# pCog102_Wifi_PSPJoy_BLED_TFT.net
KiCad netlist of a schematic drawn in EAGLE
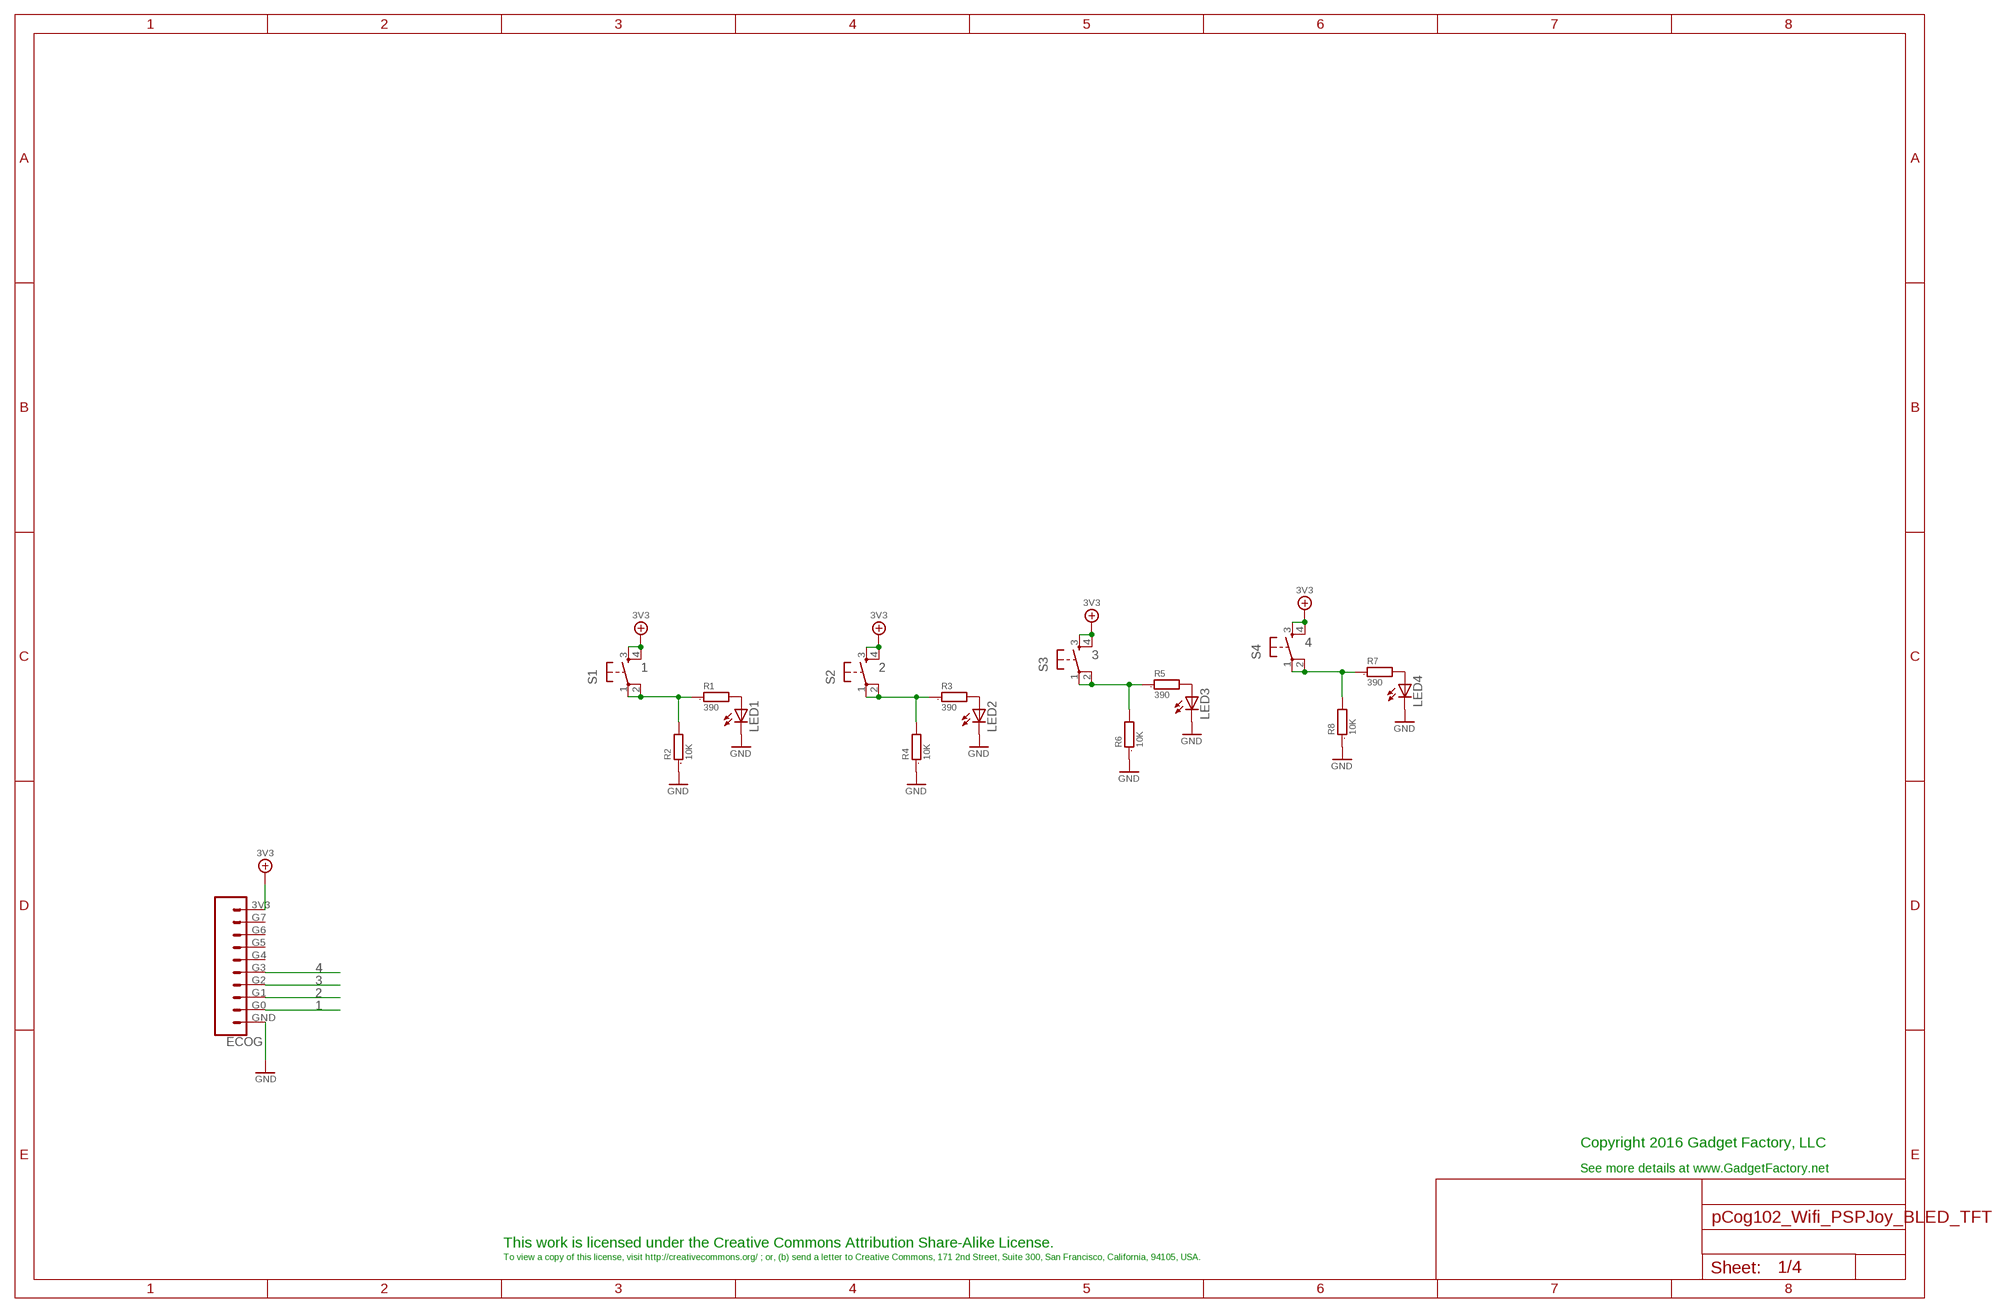
[diagram p0: schematic, sheet 1]
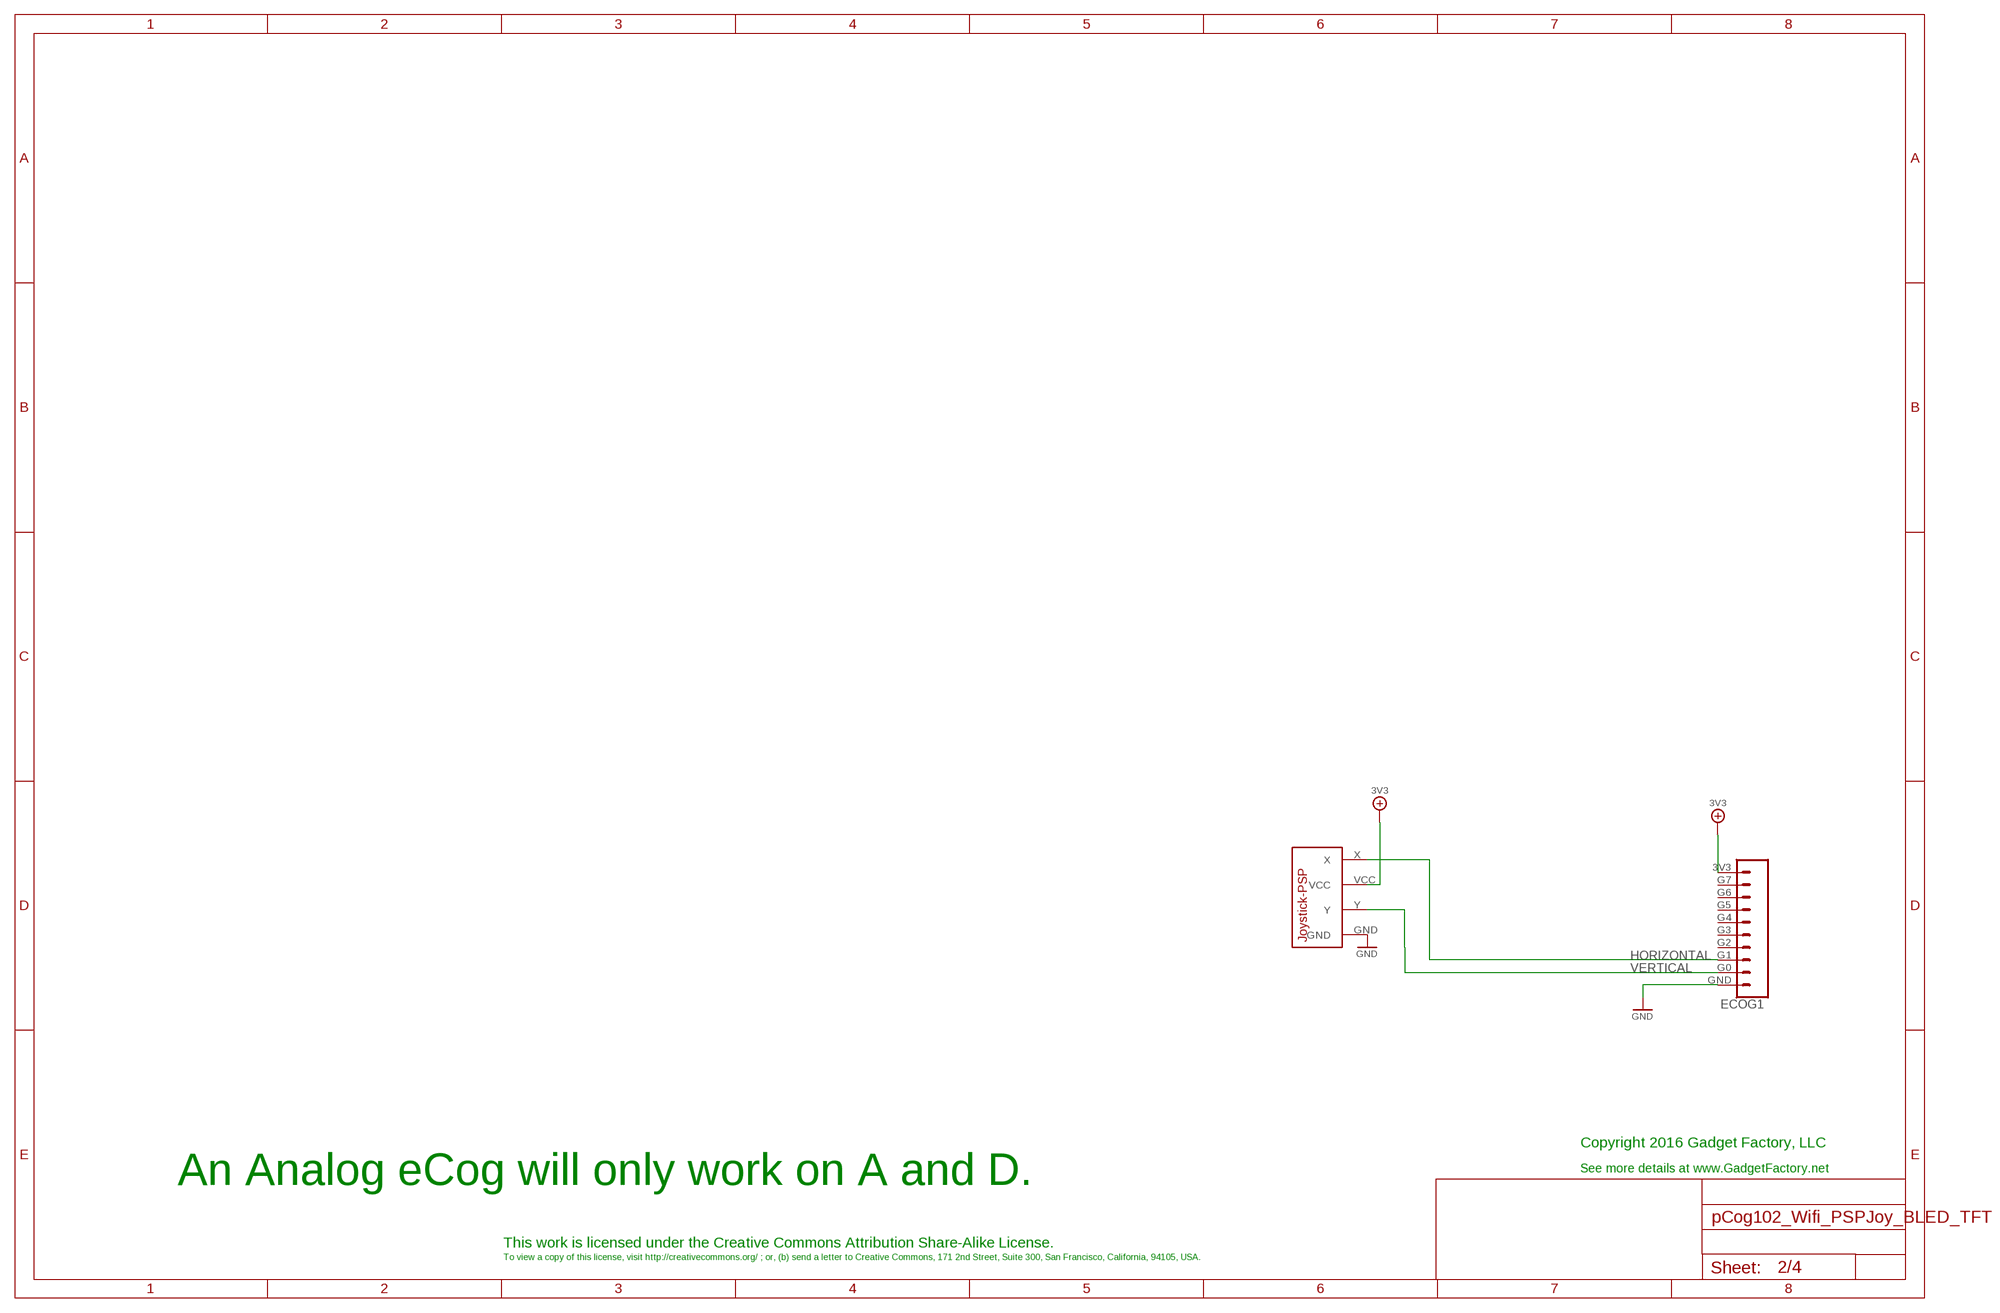
[diagram p1: schematic, sheet 2]
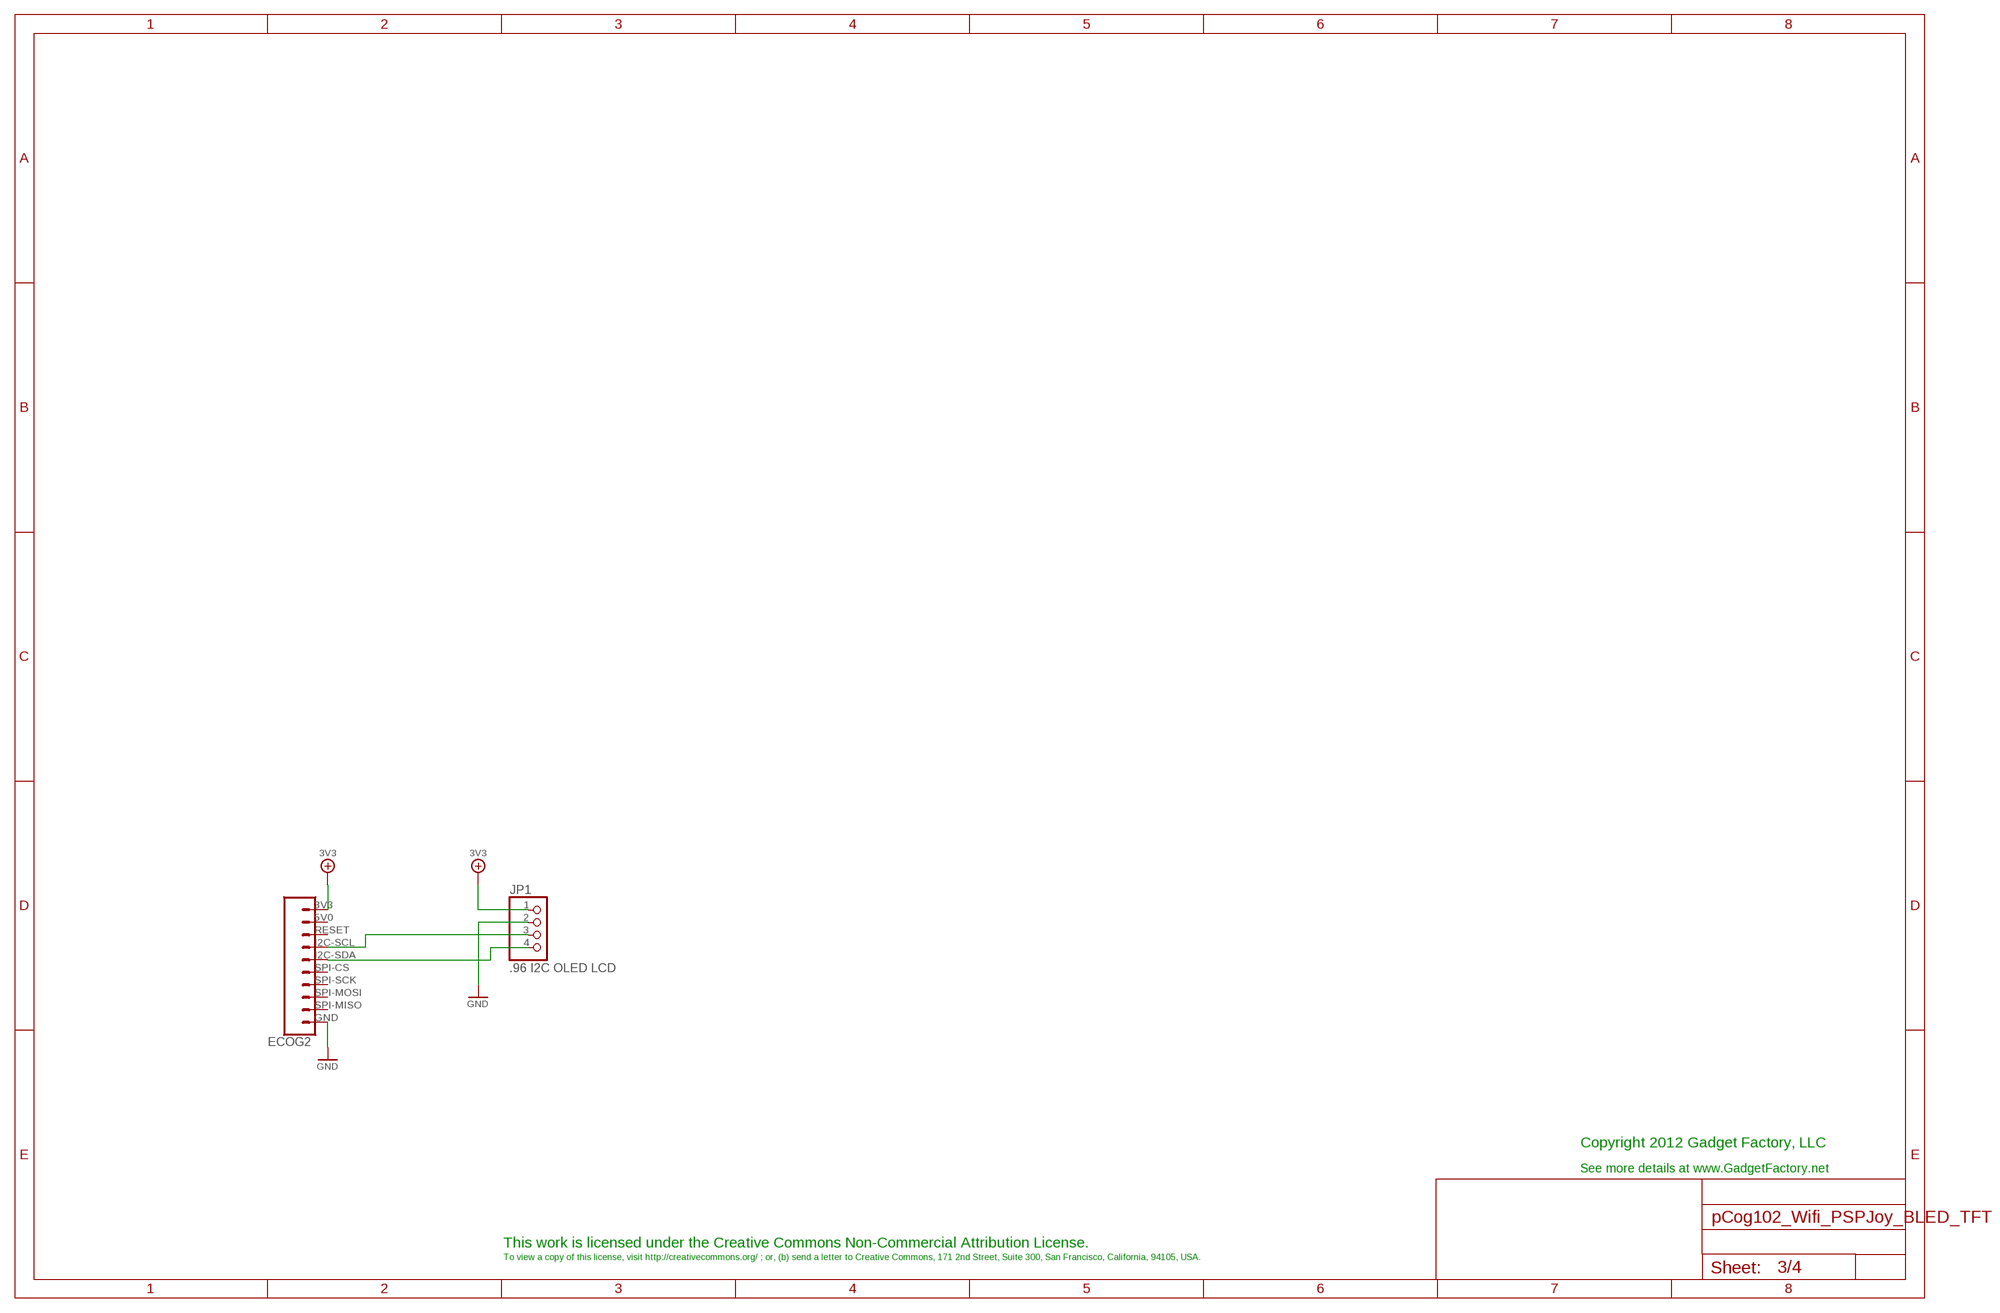
[diagram p2: schematic, sheet 3]
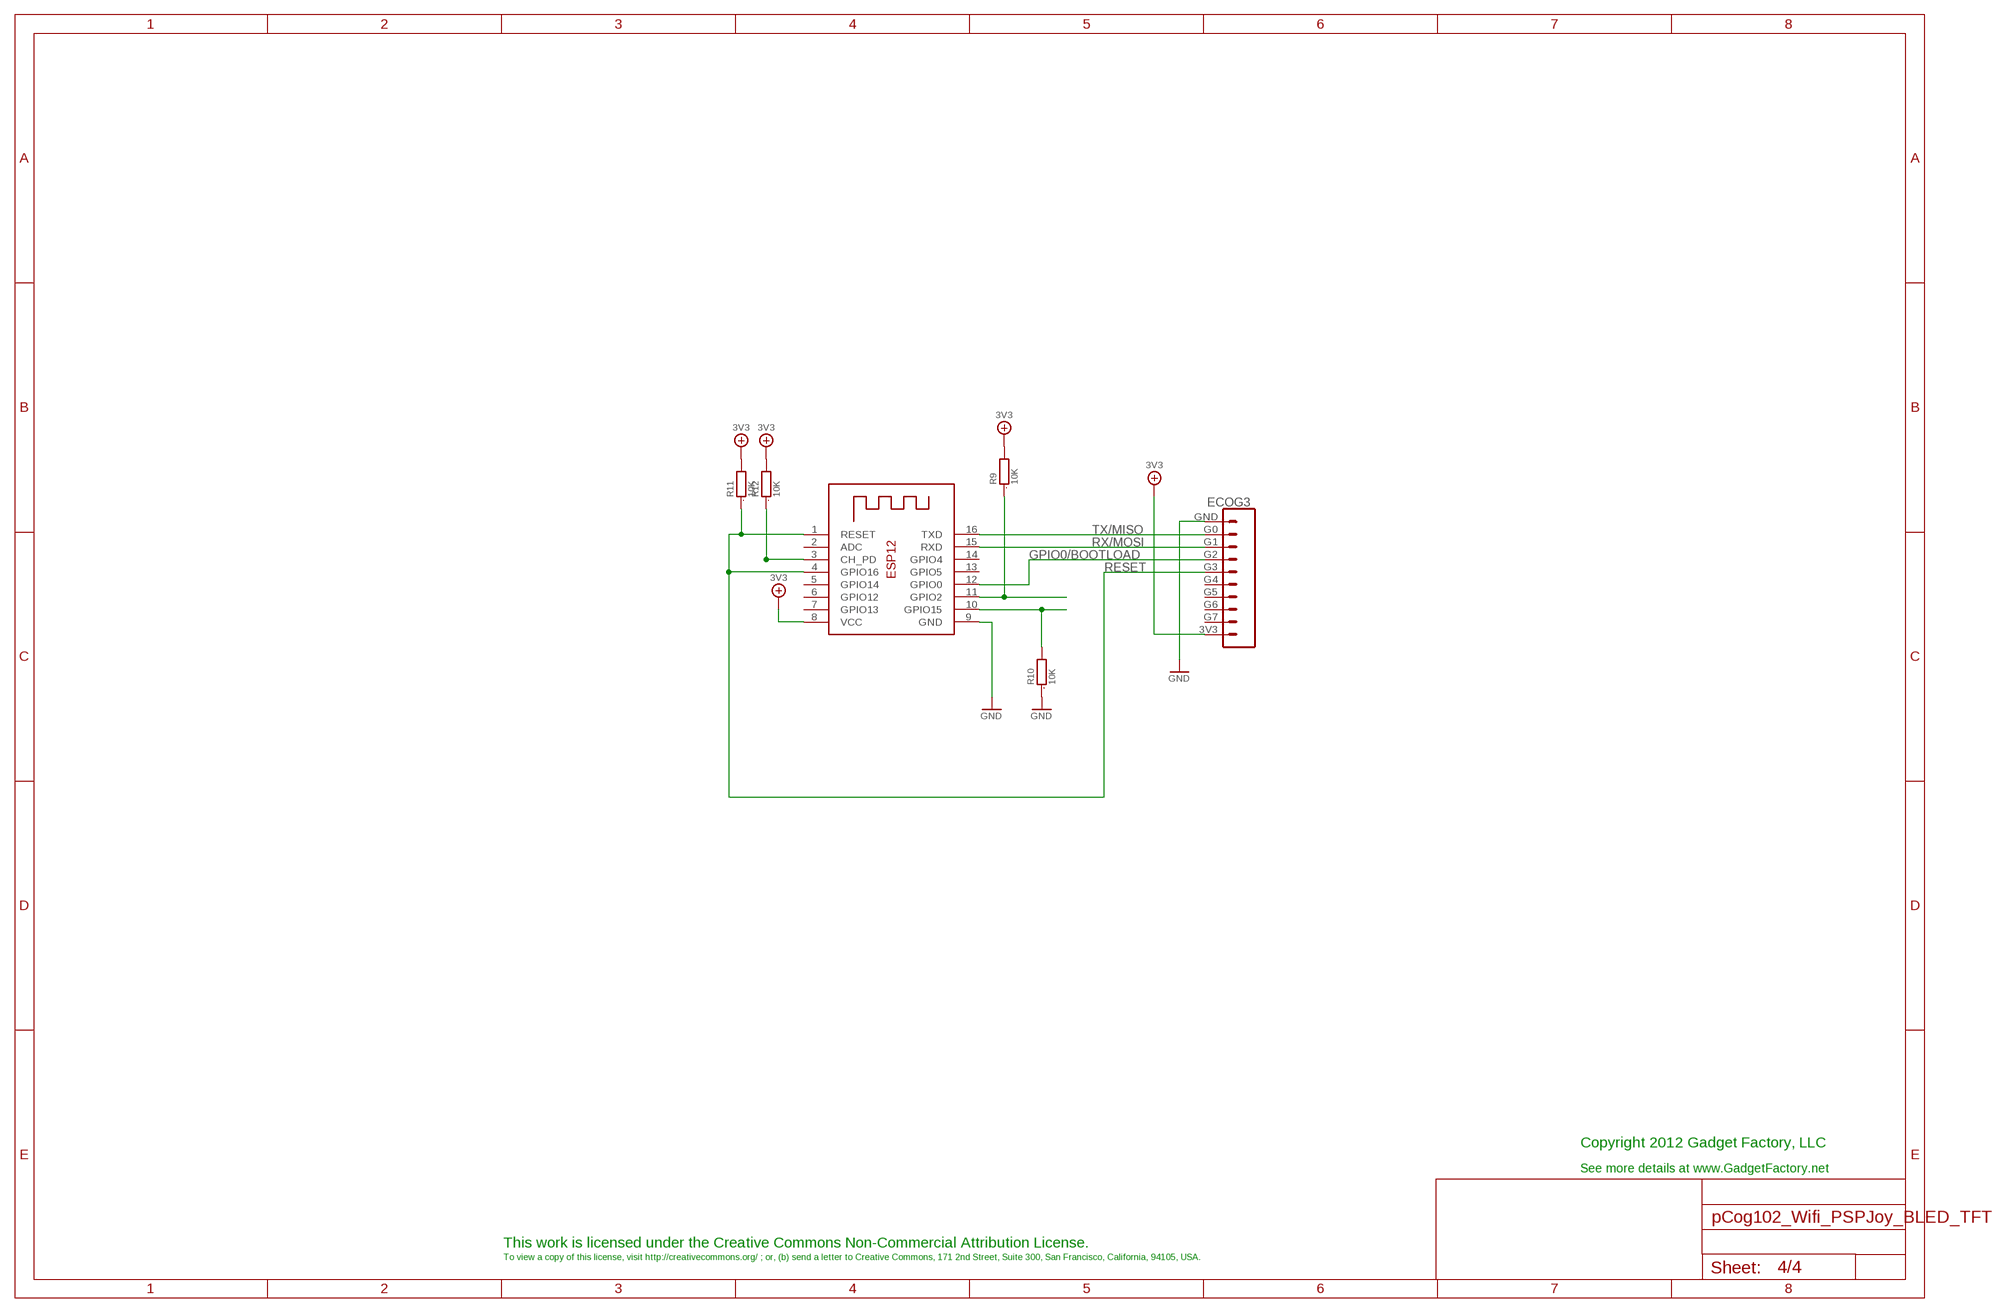
[diagram p3: schematic, sheet 4]

(export (version "E")
  (design (tool "Eeschema 10.0.6"))
  (components
    (comp (ref "ECOG2")
      (value "ECOG_BUSES_ROWECOG_BUSES_SMD")
      (footprint "eagle-import:ECOG_BUSES_SMD")
      (libsource (lib "eagle-import") (part "ECOG_BUSES_ROWECOG_BUSES_SMD"))
    )
    (comp (ref "JP1")
      (value ".96 I2C OLED LCD")
      (footprint "eagle-import:1X04")
      (libsource (lib "eagle-import") (part "PINHD-1X4"))
    )
    (comp (ref "ECOG3")
      (value "ECOG_GENERAL_ROWECOG_GENERAL_SMD")
      (footprint "eagle-import:ECOG_GENERAL_SMD")
      (libsource (lib "eagle-import") (part "ECOG_GENERAL_ROWECOG_GENERAL_SMD"))
    )
    (comp (ref "R9")
      (value "10K")
      (footprint "eagle-import:0805")
      (libsource (lib "eagle-import") (part "R0805"))
    )
    (comp (ref "R10")
      (value "10K")
      (footprint "eagle-import:0805")
      (libsource (lib "eagle-import") (part "R0805"))
    )
    (comp (ref "R11")
      (value "10K")
      (footprint "eagle-import:0805")
      (libsource (lib "eagle-import") (part "R0805"))
    )
    (comp (ref "R12")
      (value "10K")
      (footprint "eagle-import:0805")
      (libsource (lib "eagle-import") (part "R0805"))
    )
    (comp (ref "X1")
      (value "ESP-12")
      (footprint "eagle-import:ESP-12")
      (libsource (lib "eagle-import") (part "ESP-12"))
    )
    (comp (ref "ECOG")
      (value "ECOG_GENERAL_ROWECOG_GENERAL_SMD")
      (footprint "eagle-import:ECOG_GENERAL_SMD")
      (libsource (lib "eagle-import") (part "ECOG_GENERAL_ROWECOG_GENERAL_SMD"))
    )
    (comp (ref "LED1")
      (value "LEDCHIP-LED0805")
      (footprint "eagle-import:CHIP-LED0805")
      (fields
        (field (name "PARTNO") "LTST-C170KGKT,LITE-ON INC (VA),DK,160-1414-1-ND,LED GREEN CLEAR 0805 SMD, REF17")
      )
      (libsource (lib "eagle-import") (part "LEDCHIP-LED0805"))
    )
    (comp (ref "LED2")
      (value "LEDCHIP-LED0805")
      (footprint "eagle-import:CHIP-LED0805")
      (fields
        (field (name "PARTNO") "LTST-C170KGKT,LITE-ON INC (VA),DK,160-1414-1-ND,LED GREEN CLEAR 0805 SMD, REF17")
      )
      (libsource (lib "eagle-import") (part "LEDCHIP-LED0805"))
    )
    (comp (ref "LED3")
      (value "LEDCHIP-LED0805")
      (footprint "eagle-import:CHIP-LED0805")
      (fields
        (field (name "PARTNO") "LTST-C170KGKT,LITE-ON INC (VA),DK,160-1414-1-ND,LED GREEN CLEAR 0805 SMD, REF17")
      )
      (libsource (lib "eagle-import") (part "LEDCHIP-LED0805"))
    )
    (comp (ref "LED4")
      (value "LEDCHIP-LED0805")
      (footprint "eagle-import:CHIP-LED0805")
      (fields
        (field (name "PARTNO") "LTST-C170KGKT,LITE-ON INC (VA),DK,160-1414-1-ND,LED GREEN CLEAR 0805 SMD, REF17")
      )
      (libsource (lib "eagle-import") (part "LEDCHIP-LED0805"))
    )
    (comp (ref "R1")
      (value "390")
      (footprint "eagle-import:0805")
      (libsource (lib "eagle-import") (part "R0805"))
    )
    (comp (ref "R2")
      (value "10K")
      (footprint "eagle-import:0805")
      (libsource (lib "eagle-import") (part "R0805"))
    )
    (comp (ref "R3")
      (value "390")
      (footprint "eagle-import:0805")
      (libsource (lib "eagle-import") (part "R0805"))
    )
    (comp (ref "R4")
      (value "10K")
      (footprint "eagle-import:0805")
      (libsource (lib "eagle-import") (part "R0805"))
    )
    (comp (ref "R5")
      (value "390")
      (footprint "eagle-import:0805")
      (libsource (lib "eagle-import") (part "R0805"))
    )
    (comp (ref "R6")
      (value "10K")
      (footprint "eagle-import:0805")
      (libsource (lib "eagle-import") (part "R0805"))
    )
    (comp (ref "R7")
      (value "390")
      (footprint "eagle-import:0805")
      (libsource (lib "eagle-import") (part "R0805"))
    )
    (comp (ref "R8")
      (value "10K")
      (footprint "eagle-import:0805")
      (libsource (lib "eagle-import") (part "R0805"))
    )
    (comp (ref "S1")
      (value "TAC_SWITCHPTH")
      (footprint "eagle-import:TACTILE-PTH")
      (fields
        (field (name "PARTNO") "MJTP1230,Apem,dk,679-2428-ND,Tactile Switch SPST-NO Top Actuated Through Hole, REF95")
      )
      (libsource (lib "eagle-import") (part "TAC_SWITCHPTH"))
    )
    (comp (ref "S2")
      (value "TAC_SWITCHPTH")
      (footprint "eagle-import:TACTILE-PTH")
      (fields
        (field (name "PARTNO") "MJTP1230,Apem,dk,679-2428-ND,Tactile Switch SPST-NO Top Actuated Through Hole, REF95")
      )
      (libsource (lib "eagle-import") (part "TAC_SWITCHPTH"))
    )
    (comp (ref "S3")
      (value "TAC_SWITCHPTH")
      (footprint "eagle-import:TACTILE-PTH")
      (fields
        (field (name "PARTNO") "MJTP1230,Apem,dk,679-2428-ND,Tactile Switch SPST-NO Top Actuated Through Hole, REF95")
      )
      (libsource (lib "eagle-import") (part "TAC_SWITCHPTH"))
    )
    (comp (ref "S4")
      (value "TAC_SWITCHPTH")
      (footprint "eagle-import:TACTILE-PTH")
      (fields
        (field (name "PARTNO") "MJTP1230,Apem,dk,679-2428-ND,Tactile Switch SPST-NO Top Actuated Through Hole, REF95")
      )
      (libsource (lib "eagle-import") (part "TAC_SWITCHPTH"))
    )
    (comp (ref "ECOG1")
      (value "ECOG_GENERAL_ROWECOG_GENERAL_SMD")
      (footprint "eagle-import:ECOG_GENERAL_SMD")
      (libsource (lib "eagle-import") (part "ECOG_GENERAL_ROWECOG_GENERAL_SMD"))
    )
    (comp (ref "U$7")
      (value "JOYSTICK-PSP1000")
      (footprint "eagle-import:JOYSTICK-PSP1000")
      (libsource (lib "eagle-import") (part "JOYSTICK-PSP1000"))
    )
  )
  (nets
    (net (code "1") (name "1") (class "Default")
      (node (ref "ECOG") (pin "G0") (pinfunction "G0_G0") (pintype "passive"))
      (node (ref "R1") (pin "1") (pinfunction "1_1") (pintype "passive"))
      (node (ref "R2") (pin "2") (pinfunction "2_2") (pintype "passive"))
      (node (ref "S1") (pin "1") (pinfunction "1_1") (pintype "passive"))
      (node (ref "S1") (pin "2") (pinfunction "2_2") (pintype "passive"))
    )
    (net (code "2") (name "2") (class "Default")
      (node (ref "ECOG") (pin "G1") (pinfunction "G1_G1") (pintype "passive"))
      (node (ref "R3") (pin "1") (pinfunction "1_1") (pintype "passive"))
      (node (ref "R4") (pin "2") (pinfunction "2_2") (pintype "passive"))
      (node (ref "S2") (pin "1") (pinfunction "1_1") (pintype "passive"))
      (node (ref "S2") (pin "2") (pinfunction "2_2") (pintype "passive"))
    )
    (net (code "3") (name "3") (class "Default")
      (node (ref "ECOG") (pin "G2") (pinfunction "G2_G2") (pintype "passive"))
      (node (ref "R5") (pin "1") (pinfunction "1_1") (pintype "passive"))
      (node (ref "R6") (pin "2") (pinfunction "2_2") (pintype "passive"))
      (node (ref "S3") (pin "1") (pinfunction "1_1") (pintype "passive"))
      (node (ref "S3") (pin "2") (pinfunction "2_2") (pintype "passive"))
    )
    (net (code "4") (name "3V3") (class "Default")
      (node (ref "ECOG") (pin "3V3") (pinfunction "3V3_3V3") (pintype "power_in"))
      (node (ref "ECOG1") (pin "3V3") (pinfunction "3V3_3V3") (pintype "power_in"))
      (node (ref "ECOG2") (pin "3V3") (pinfunction "3V3_3V3") (pintype "passive"))
      (node (ref "ECOG3") (pin "3V3") (pinfunction "3V3_3V3") (pintype "power_in"))
      (node (ref "JP1") (pin "1") (pinfunction "1_1") (pintype "passive"))
      (node (ref "R11") (pin "2") (pinfunction "2_2") (pintype "passive"))
      (node (ref "R12") (pin "2") (pinfunction "2_2") (pintype "passive"))
      (node (ref "R9") (pin "2") (pinfunction "2_2") (pintype "passive"))
      (node (ref "S1") (pin "3") (pinfunction "3_3") (pintype "passive"))
      (node (ref "S1") (pin "4") (pinfunction "4_4") (pintype "passive"))
      (node (ref "S2") (pin "3") (pinfunction "3_3") (pintype "passive"))
      (node (ref "S2") (pin "4") (pinfunction "4_4") (pintype "passive"))
      (node (ref "S3") (pin "3") (pinfunction "3_3") (pintype "passive"))
      (node (ref "S3") (pin "4") (pinfunction "4_4") (pintype "passive"))
      (node (ref "S4") (pin "3") (pinfunction "3_3") (pintype "passive"))
      (node (ref "S4") (pin "4") (pinfunction "4_4") (pintype "passive"))
      (node (ref "U$7") (pin "VCC") (pinfunction "VCC_VCC") (pintype "bidirectional"))
      (node (ref "X1") (pin "8") (pinfunction "VCC_8") (pintype "power_in"))
    )
    (net (code "5") (name "4") (class "Default")
      (node (ref "ECOG") (pin "G3") (pinfunction "G3_G3") (pintype "passive"))
      (node (ref "R7") (pin "1") (pinfunction "1_1") (pintype "passive"))
      (node (ref "R8") (pin "2") (pinfunction "2_2") (pintype "passive"))
      (node (ref "S4") (pin "1") (pinfunction "1_1") (pintype "passive"))
      (node (ref "S4") (pin "2") (pinfunction "2_2") (pintype "passive"))
    )
    (net (code "6") (name "GND") (class "Default")
      (node (ref "ECOG") (pin "GND") (pinfunction "GND_GND") (pintype "power_in"))
      (node (ref "ECOG1") (pin "GND") (pinfunction "GND_GND") (pintype "power_in"))
      (node (ref "ECOG2") (pin "GND") (pinfunction "GND_GND") (pintype "passive"))
      (node (ref "ECOG3") (pin "GND") (pinfunction "GND_GND") (pintype "power_in"))
      (node (ref "JP1") (pin "2") (pinfunction "2_2") (pintype "passive"))
      (node (ref "LED1") (pin "C") (pinfunction "C_C") (pintype "passive"))
      (node (ref "LED2") (pin "C") (pinfunction "C_C") (pintype "passive"))
      (node (ref "LED3") (pin "C") (pinfunction "C_C") (pintype "passive"))
      (node (ref "LED4") (pin "C") (pinfunction "C_C") (pintype "passive"))
      (node (ref "R10") (pin "1") (pinfunction "1_1") (pintype "passive"))
      (node (ref "R2") (pin "1") (pinfunction "1_1") (pintype "passive"))
      (node (ref "R4") (pin "1") (pinfunction "1_1") (pintype "passive"))
      (node (ref "R6") (pin "1") (pinfunction "1_1") (pintype "passive"))
      (node (ref "R8") (pin "1") (pinfunction "1_1") (pintype "passive"))
      (node (ref "U$7") (pin "GND") (pinfunction "GND_GND") (pintype "bidirectional"))
      (node (ref "X1") (pin "9") (pinfunction "GND_9") (pintype "power_in"))
    )
    (net (code "7") (name "GPIO0{slash}BOOTLOAD") (class "Default")
      (node (ref "ECOG3") (pin "G2") (pinfunction "G2_G2") (pintype "passive"))
      (node (ref "X1") (pin "12") (pinfunction "GPIO0_12") (pintype "bidirectional"))
    )
    (net (code "8") (name "HORIZONTAL") (class "Default")
      (node (ref "ECOG1") (pin "G1") (pinfunction "G1_G1") (pintype "passive"))
      (node (ref "U$7") (pin "X") (pinfunction "X_X") (pintype "bidirectional"))
    )
    (net (code "9") (name "Net-(ECOG2-PadI2C-SCL)") (class "Default")
      (node (ref "ECOG2") (pin "I2C-SCL") (pinfunction "I2C-SCL_I2C-SCL") (pintype "passive"))
      (node (ref "JP1") (pin "3") (pinfunction "3_3") (pintype "passive"))
    )
    (net (code "10") (name "Net-(ECOG2-PadI2C-SDA)") (class "Default")
      (node (ref "ECOG2") (pin "I2C-SDA") (pinfunction "I2C-SDA_I2C-SDA") (pintype "passive"))
      (node (ref "JP1") (pin "4") (pinfunction "4_4") (pintype "passive"))
    )
    (net (code "11") (name "Net-(LED1-PadA)") (class "Default")
      (node (ref "LED1") (pin "A") (pinfunction "A_A") (pintype "passive"))
      (node (ref "R1") (pin "2") (pinfunction "2_2") (pintype "passive"))
    )
    (net (code "12") (name "Net-(LED2-PadA)") (class "Default")
      (node (ref "LED2") (pin "A") (pinfunction "A_A") (pintype "passive"))
      (node (ref "R3") (pin "2") (pinfunction "2_2") (pintype "passive"))
    )
    (net (code "13") (name "Net-(LED3-PadA)") (class "Default")
      (node (ref "LED3") (pin "A") (pinfunction "A_A") (pintype "passive"))
      (node (ref "R5") (pin "2") (pinfunction "2_2") (pintype "passive"))
    )
    (net (code "14") (name "Net-(LED4-PadA)") (class "Default")
      (node (ref "LED4") (pin "A") (pinfunction "A_A") (pintype "passive"))
      (node (ref "R7") (pin "2") (pinfunction "2_2") (pintype "passive"))
    )
    (net (code "15") (name "Net-(X1-CH_PD)") (class "Default")
      (node (ref "R12") (pin "1") (pinfunction "1_1") (pintype "passive"))
      (node (ref "X1") (pin "3") (pinfunction "CH_PD_3") (pintype "input"))
    )
    (net (code "16") (name "Net-(X1-GPIO2)") (class "Default")
      (node (ref "R9") (pin "1") (pinfunction "1_1") (pintype "passive"))
      (node (ref "X1") (pin "11") (pinfunction "GPIO2_11") (pintype "bidirectional"))
    )
    (net (code "17") (name "Net-(X1-GPIO15)") (class "Default")
      (node (ref "R10") (pin "2") (pinfunction "2_2") (pintype "passive"))
      (node (ref "X1") (pin "10") (pinfunction "GPIO15_10") (pintype "bidirectional"))
    )
    (net (code "18") (name "RESET") (class "Default")
      (node (ref "ECOG3") (pin "G3") (pinfunction "G3_G3") (pintype "passive"))
      (node (ref "R11") (pin "1") (pinfunction "1_1") (pintype "passive"))
      (node (ref "X1") (pin "1") (pinfunction "RESET_1") (pintype "input"))
      (node (ref "X1") (pin "4") (pinfunction "GPIO16_4") (pintype "bidirectional"))
    )
    (net (code "19") (name "RX{slash}MOSI") (class "Default")
      (node (ref "ECOG3") (pin "G1") (pinfunction "G1_G1") (pintype "passive"))
      (node (ref "X1") (pin "15") (pinfunction "RXD_15") (pintype "input"))
    )
    (net (code "20") (name "TX{slash}MISO") (class "Default")
      (node (ref "ECOG3") (pin "G0") (pinfunction "G0_G0") (pintype "passive"))
      (node (ref "X1") (pin "16") (pinfunction "TXD_16") (pintype "output"))
    )
    (net (code "21") (name "VERTICAL") (class "Default")
      (node (ref "ECOG1") (pin "G0") (pinfunction "G0_G0") (pintype "passive"))
      (node (ref "U$7") (pin "Y") (pinfunction "Y_Y") (pintype "bidirectional"))
    )
    (net (code "22") (name "unconnected-(ECOG-PadG4)") (class "Default")
      (node (ref "ECOG") (pin "G4") (pinfunction "G4_G4") (pintype "passive"))
    )
    (net (code "23") (name "unconnected-(ECOG-PadG5)") (class "Default")
      (node (ref "ECOG") (pin "G5") (pinfunction "G5_G5") (pintype "passive"))
    )
    (net (code "24") (name "unconnected-(ECOG-PadG6)") (class "Default")
      (node (ref "ECOG") (pin "G6") (pinfunction "G6_G6") (pintype "passive"))
    )
    (net (code "25") (name "unconnected-(ECOG-PadG7)") (class "Default")
      (node (ref "ECOG") (pin "G7") (pinfunction "G7_G7") (pintype "passive"))
    )
    (net (code "26") (name "unconnected-(ECOG1-PadG2)") (class "Default")
      (node (ref "ECOG1") (pin "G2") (pinfunction "G2_G2") (pintype "passive"))
    )
    (net (code "27") (name "unconnected-(ECOG1-PadG3)") (class "Default")
      (node (ref "ECOG1") (pin "G3") (pinfunction "G3_G3") (pintype "passive"))
    )
    (net (code "28") (name "unconnected-(ECOG1-PadG4)") (class "Default")
      (node (ref "ECOG1") (pin "G4") (pinfunction "G4_G4") (pintype "passive"))
    )
    (net (code "29") (name "unconnected-(ECOG1-PadG5)") (class "Default")
      (node (ref "ECOG1") (pin "G5") (pinfunction "G5_G5") (pintype "passive"))
    )
    (net (code "30") (name "unconnected-(ECOG1-PadG6)") (class "Default")
      (node (ref "ECOG1") (pin "G6") (pinfunction "G6_G6") (pintype "passive"))
    )
    (net (code "31") (name "unconnected-(ECOG1-PadG7)") (class "Default")
      (node (ref "ECOG1") (pin "G7") (pinfunction "G7_G7") (pintype "passive"))
    )
    (net (code "32") (name "unconnected-(ECOG2-Pad5V0)") (class "Default")
      (node (ref "ECOG2") (pin "5V0") (pinfunction "5V0_5V0") (pintype "passive"))
    )
    (net (code "33") (name "unconnected-(ECOG2-PadRESET)") (class "Default")
      (node (ref "ECOG2") (pin "RESET") (pinfunction "RESET_RESET") (pintype "passive"))
    )
    (net (code "34") (name "unconnected-(ECOG2-PadSPI-CS)") (class "Default")
      (node (ref "ECOG2") (pin "SPI-CS") (pinfunction "SPI-CS_SPI-CS") (pintype "passive"))
    )
    (net (code "35") (name "unconnected-(ECOG2-PadSPI-MISO)") (class "Default")
      (node (ref "ECOG2") (pin "SPI-MISO") (pinfunction "SPI-MISO_SPI-MISO") (pintype "passive"))
    )
    (net (code "36") (name "unconnected-(ECOG2-PadSPI-MOSI)") (class "Default")
      (node (ref "ECOG2") (pin "SPI-MOSI") (pinfunction "SPI-MOSI_SPI-MOSI") (pintype "passive"))
    )
    (net (code "37") (name "unconnected-(ECOG2-PadSPI-SCK)") (class "Default")
      (node (ref "ECOG2") (pin "SPI-SCK") (pinfunction "SPI-SCK_SPI-SCK") (pintype "passive"))
    )
    (net (code "38") (name "unconnected-(ECOG3-PadG4)") (class "Default")
      (node (ref "ECOG3") (pin "G4") (pinfunction "G4_G4") (pintype "passive"))
    )
    (net (code "39") (name "unconnected-(ECOG3-PadG5)") (class "Default")
      (node (ref "ECOG3") (pin "G5") (pinfunction "G5_G5") (pintype "passive"))
    )
    (net (code "40") (name "unconnected-(ECOG3-PadG6)") (class "Default")
      (node (ref "ECOG3") (pin "G6") (pinfunction "G6_G6") (pintype "passive"))
    )
    (net (code "41") (name "unconnected-(ECOG3-PadG7)") (class "Default")
      (node (ref "ECOG3") (pin "G7") (pinfunction "G7_G7") (pintype "passive"))
    )
    (net (code "42") (name "unconnected-(X1-ADC-Pad2)") (class "Default")
      (node (ref "X1") (pin "2") (pinfunction "ADC_2") (pintype "passive"))
    )
    (net (code "43") (name "unconnected-(X1-GPIO4-Pad14)") (class "Default")
      (node (ref "X1") (pin "14") (pinfunction "GPIO4_14") (pintype "bidirectional"))
    )
    (net (code "44") (name "unconnected-(X1-GPIO5-Pad13)") (class "Default")
      (node (ref "X1") (pin "13") (pinfunction "GPIO5_13") (pintype "bidirectional"))
    )
    (net (code "45") (name "unconnected-(X1-GPIO12-Pad6)") (class "Default")
      (node (ref "X1") (pin "6") (pinfunction "GPIO12_6") (pintype "bidirectional"))
    )
    (net (code "46") (name "unconnected-(X1-GPIO13-Pad7)") (class "Default")
      (node (ref "X1") (pin "7") (pinfunction "GPIO13_7") (pintype "bidirectional"))
    )
    (net (code "47") (name "unconnected-(X1-GPIO14-Pad5)") (class "Default")
      (node (ref "X1") (pin "5") (pinfunction "GPIO14_5") (pintype "bidirectional"))
    )
  )
)
